# Shematic.net
KiCad netlist of a schematic drawn in Altium Designer
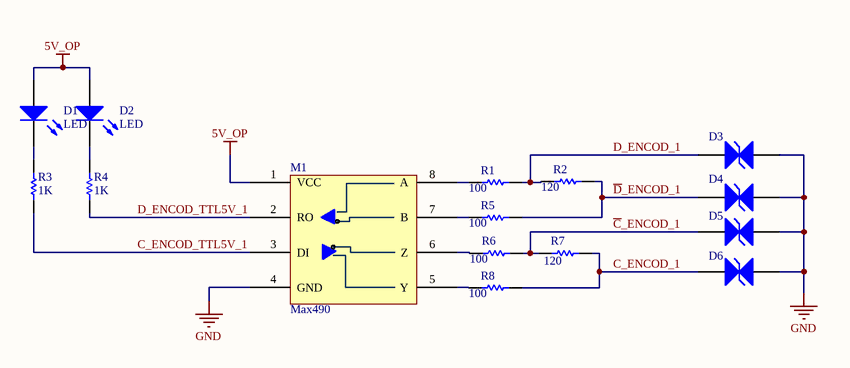
[diagram p0: Shematic.SchDoc]

(export (version "E")
  (design (tool "Eeschema 10.0.6"))
  (components
    (comp (ref "D1")
      (value "LED")
      (description "Typical INFRARED GaAs LED")
      (fields (field (name "PUBLISHER") "Altium Limited"))
      (libsource (lib "Miscellaneous Devices") (part "LED0"))
    )
    (comp (ref "D2")
      (value "LED")
      (description "Typical INFRARED GaAs LED")
      (fields (field (name "PUBLISHER") "Altium Limited"))
      (libsource (lib "Miscellaneous Devices") (part "LED0"))
    )
    (comp (ref "D3")
      (value "Diode_ESD")
      (description "ESD Biderction Diode. SMB Package. 6volt.")
      (libsource (lib "Diode_ESD") (part "Diode_ESD"))
    )
    (comp (ref "D4")
      (value "Diode_ESD")
      (description "ESD Biderction Diode. SMB Package. 6volt.")
      (libsource (lib "Diode_ESD") (part "Diode_ESD"))
    )
    (comp (ref "D5")
      (value "Diode_ESD")
      (description "ESD Biderction Diode. SMB Package. 6volt.")
      (libsource (lib "Diode_ESD") (part "Diode_ESD"))
    )
    (comp (ref "D6")
      (value "Diode_ESD")
      (description "ESD Biderction Diode. SMB Package. 6volt.")
      (libsource (lib "Diode_ESD") (part "Diode_ESD"))
    )
    (comp (ref "M1")
      (value "Max490")
      (footprint "Max490")
      (description "Single Transmitter/Receiver RS-422/RS-485 8-Pin SOIC N")
      (fields (field (name "MANUFACTURER") "Maxim") (field (name "MANUFACTURER PART NUMBER") "MAX490ESA+"))
      (libsource (lib "Max490") (part "Max490"))
    )
    (comp (ref "R1")
      (value "100")
      (description "Resistor")
      (fields (field (name "Comment") "Res") (field (name "PUBLISHER") "Altium Limited"))
      (libsource (lib "Miscellaneous Devices") (part "Res1"))
    )
    (comp (ref "R2")
      (value "120")
      (description "Resistor")
      (fields (field (name "Comment") "Res") (field (name "PUBLISHER") "Altium Limited"))
      (libsource (lib "Miscellaneous Devices") (part "Res1"))
    )
    (comp (ref "R3")
      (value "1K")
      (description "Resistor")
      (fields (field (name "Comment") "Res") (field (name "PUBLISHER") "Altium Limited"))
      (libsource (lib "Miscellaneous Devices") (part "Res1"))
    )
    (comp (ref "R4")
      (value "1K")
      (description "Resistor")
      (fields (field (name "Comment") "Res") (field (name "PUBLISHER") "Altium Limited"))
      (libsource (lib "Miscellaneous Devices") (part "Res1"))
    )
    (comp (ref "R5")
      (value "100")
      (description "Resistor")
      (fields (field (name "Comment") "Res") (field (name "PUBLISHER") "Altium Limited"))
      (libsource (lib "Miscellaneous Devices") (part "Res1"))
    )
    (comp (ref "R6")
      (value "100")
      (description "Resistor")
      (fields (field (name "Comment") "Res") (field (name "PUBLISHER") "Altium Limited"))
      (libsource (lib "Miscellaneous Devices") (part "Res1"))
    )
    (comp (ref "R7")
      (value "120")
      (description "Resistor")
      (fields (field (name "Comment") "Res") (field (name "PUBLISHER") "Altium Limited"))
      (libsource (lib "Miscellaneous Devices") (part "Res1"))
    )
    (comp (ref "R8")
      (value "100")
      (description "Resistor")
      (fields (field (name "Comment") "Res") (field (name "PUBLISHER") "Altium Limited"))
      (libsource (lib "Miscellaneous Devices") (part "Res1"))
    )
  )
  (nets
    (net (code "1") (name "/C_ENCOD_1") (class "Default")
      (node (ref "D6") (pin "2") (pinfunction "K_2") (pintype "passive"))
      (node (ref "R7") (pin "2") (pinfunction "2_2") (pintype "passive"))
      (node (ref "R8") (pin "2") (pinfunction "2_2") (pintype "passive"))
    )
    (net (code "2") (name "/C_ENCOD_TTL5V_1") (class "Default")
      (node (ref "M1") (pin "3") (pinfunction "DI_3") (pintype "passive"))
      (node (ref "R3") (pin "1") (pinfunction "1_1") (pintype "passive"))
    )
    (net (code "3") (name "/D_ENCOD_1") (class "Default")
      (node (ref "D3") (pin "2") (pinfunction "K_2") (pintype "passive"))
      (node (ref "R1") (pin "2") (pinfunction "2_2") (pintype "passive"))
      (node (ref "R2") (pin "1") (pinfunction "1_1") (pintype "passive"))
    )
    (net (code "4") (name "/D_ENCOD_TTL5V_1") (class "Default")
      (node (ref "M1") (pin "2") (pinfunction "RO_2") (pintype "passive"))
      (node (ref "R4") (pin "1") (pinfunction "1_1") (pintype "passive"))
    )
    (net (code "5") (name "/~{C}_ENCOD_1") (class "Default")
      (node (ref "D5") (pin "2") (pinfunction "K_2") (pintype "passive"))
      (node (ref "R6") (pin "2") (pinfunction "2_2") (pintype "passive"))
      (node (ref "R7") (pin "1") (pinfunction "1_1") (pintype "passive"))
    )
    (net (code "6") (name "/~{D}_ENCOD_1") (class "Default")
      (node (ref "D4") (pin "2") (pinfunction "K_2") (pintype "passive"))
      (node (ref "R2") (pin "2") (pinfunction "2_2") (pintype "passive"))
      (node (ref "R5") (pin "2") (pinfunction "2_2") (pintype "passive"))
    )
    (net (code "7") (name "5V_OP") (class "Default")
      (node (ref "D1") (pin "1") (pinfunction "A_1") (pintype "passive"))
      (node (ref "D2") (pin "1") (pinfunction "A_1") (pintype "passive"))
      (node (ref "M1") (pin "1") (pinfunction "VCC_1") (pintype "passive"))
    )
    (net (code "8") (name "GND") (class "Default")
      (node (ref "D3") (pin "1") (pinfunction "A_1") (pintype "passive"))
      (node (ref "D4") (pin "1") (pinfunction "A_1") (pintype "passive"))
      (node (ref "D5") (pin "1") (pinfunction "A_1") (pintype "passive"))
      (node (ref "D6") (pin "1") (pinfunction "A_1") (pintype "passive"))
      (node (ref "M1") (pin "4") (pinfunction "GND_4") (pintype "passive"))
    )
    (net (code "9") (name "Net-(D1-K)") (class "Default")
      (node (ref "D1") (pin "2") (pinfunction "K_2") (pintype "passive"))
      (node (ref "R3") (pin "2") (pinfunction "2_2") (pintype "passive"))
    )
    (net (code "10") (name "Net-(D2-K)") (class "Default")
      (node (ref "D2") (pin "2") (pinfunction "K_2") (pintype "passive"))
      (node (ref "R4") (pin "2") (pinfunction "2_2") (pintype "passive"))
    )
    (net (code "11") (name "Net-(M1-A)") (class "Default")
      (node (ref "M1") (pin "8") (pinfunction "A_8") (pintype "passive"))
      (node (ref "R1") (pin "1") (pinfunction "1_1") (pintype "passive"))
    )
    (net (code "12") (name "Net-(M1-B)") (class "Default")
      (node (ref "M1") (pin "7") (pinfunction "B_7") (pintype "passive"))
      (node (ref "R5") (pin "1") (pinfunction "1_1") (pintype "passive"))
    )
    (net (code "13") (name "Net-(M1-Y)") (class "Default")
      (node (ref "M1") (pin "5") (pinfunction "Y_5") (pintype "passive"))
      (node (ref "R8") (pin "1") (pinfunction "1_1") (pintype "passive"))
    )
    (net (code "14") (name "Net-(M1-Z)") (class "Default")
      (node (ref "M1") (pin "6") (pinfunction "Z_6") (pintype "passive"))
      (node (ref "R6") (pin "1") (pinfunction "1_1") (pintype "passive"))
    )
  )
)
